# rtc.net
KiCad netlist of a schematic drawn in EAGLE
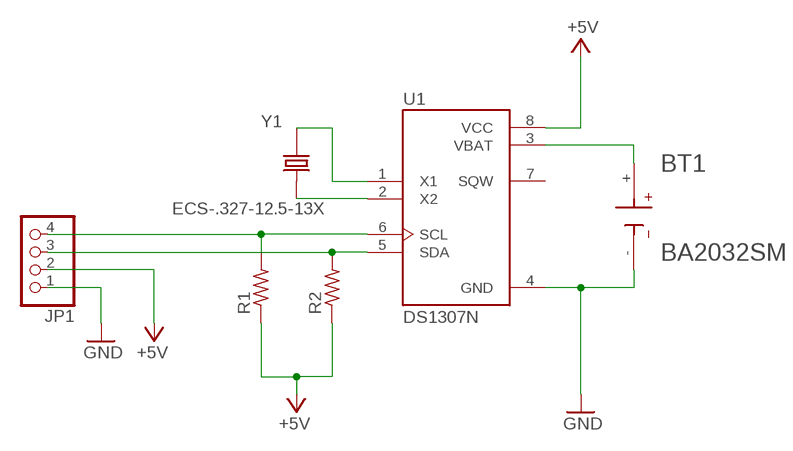
[diagram p0: schematic, sheet 1]

(export (version "E")
  (design (tool "Eeschema 10.0.6"))
  (components
    (comp (ref "BT1")
      (value "BA2032SM")
      (footprint "eagle-import:BAT_BA2032SM")
      (fields (field (name "DIGI-KEY_PART_NUMBER") "BA2032SM-ND") (field (name "MF") "MPD"))
      (libsource (lib "eagle-import") (part "BA2032SM"))
    )
    (comp (ref "JP1")
      (value "PINHD-1X4")
      (footprint "eagle-import:1X04")
      (libsource (lib "eagle-import") (part "PINHD-1X4"))
    )
    (comp (ref "R1")
      (value "R-US_R0805")
      (footprint "eagle-import:R0805")
      (libsource (lib "eagle-import") (part "R-US_R0805"))
    )
    (comp (ref "R2")
      (value "R-US_R0805")
      (footprint "eagle-import:R0805")
      (libsource (lib "eagle-import") (part "R-US_R0805"))
    )
    (comp (ref "U1")
      (value "DS1307N")
      (footprint "eagle-import:DIP762W47P254L991H457Q8")
      (fields
        (field (name "DIGI-KEY_PART_NUMBER") "DS1307N+-ND")
        (field (name "MF") "Maxim Integrated")
        (field (name "MP") "DS1307N+")
      )
      (libsource (lib "eagle-import") (part "DS1307N"))
    )
    (comp (ref "Y1")
      (value "ECS-.327-12.5-13X")
      (footprint "eagle-import:XTAL_ECS-.327-12.5-13X")
      (fields (field (name "DIGI-KEY_PART_NUMBER") "X1124-ND") (field (name "MF") "ECS Inc."))
      (libsource (lib "eagle-import") (part "ECS-.327-12.5-13X"))
    )
  )
  (nets
    (net (code "1") (name "+5V") (class "Default")
      (node (ref "JP1") (pin "2") (pinfunction "2_2") (pintype "passive"))
      (node (ref "R1") (pin "1") (pinfunction "1_1") (pintype "passive"))
      (node (ref "R2") (pin "1") (pinfunction "1_1") (pintype "passive"))
      (node (ref "U1") (pin "8") (pinfunction "VCC_8") (pintype "power_in"))
    )
    (net (code "2") (name "GND") (class "Default")
      (node (ref "BT1") (pin "-") (pinfunction "-_-") (pintype "passive"))
      (node (ref "JP1") (pin "1") (pinfunction "1_1") (pintype "passive"))
      (node (ref "U1") (pin "4") (pinfunction "GND_4") (pintype "power_in"))
    )
    (net (code "3") (name "Net-(U1-SCL)") (class "Default")
      (node (ref "JP1") (pin "4") (pinfunction "4_4") (pintype "passive"))
      (node (ref "R1") (pin "2") (pinfunction "2_2") (pintype "passive"))
      (node (ref "U1") (pin "6") (pinfunction "SCL_6") (pintype "input"))
    )
    (net (code "4") (name "Net-(U1-SDA)") (class "Default")
      (node (ref "JP1") (pin "3") (pinfunction "3_3") (pintype "passive"))
      (node (ref "R2") (pin "2") (pinfunction "2_2") (pintype "passive"))
      (node (ref "U1") (pin "5") (pinfunction "SDA_5") (pintype "bidirectional"))
    )
    (net (code "5") (name "Net-(U1-VBAT)") (class "Default")
      (node (ref "BT1") (pin "+") (pinfunction "+_+") (pintype "passive"))
      (node (ref "U1") (pin "3") (pinfunction "VBAT_3") (pintype "power_in"))
    )
    (net (code "6") (name "Net-(U1-X1)") (class "Default")
      (node (ref "U1") (pin "1") (pinfunction "X1_1") (pintype "input"))
      (node (ref "Y1") (pin "1") (pinfunction "1_1") (pintype "passive"))
    )
    (net (code "7") (name "Net-(U1-X2)") (class "Default")
      (node (ref "U1") (pin "2") (pinfunction "X2_2") (pintype "output"))
      (node (ref "Y1") (pin "2") (pinfunction "2_2") (pintype "passive"))
    )
    (net (code "8") (name "unconnected-(U1-SQW-Pad7)") (class "Default")
      (node (ref "U1") (pin "7") (pinfunction "SQW_7") (pintype "output"))
    )
  )
)
